# Electric_Mokka_Pot.net
KiCad netlist of a schematic drawn in EasyEDA
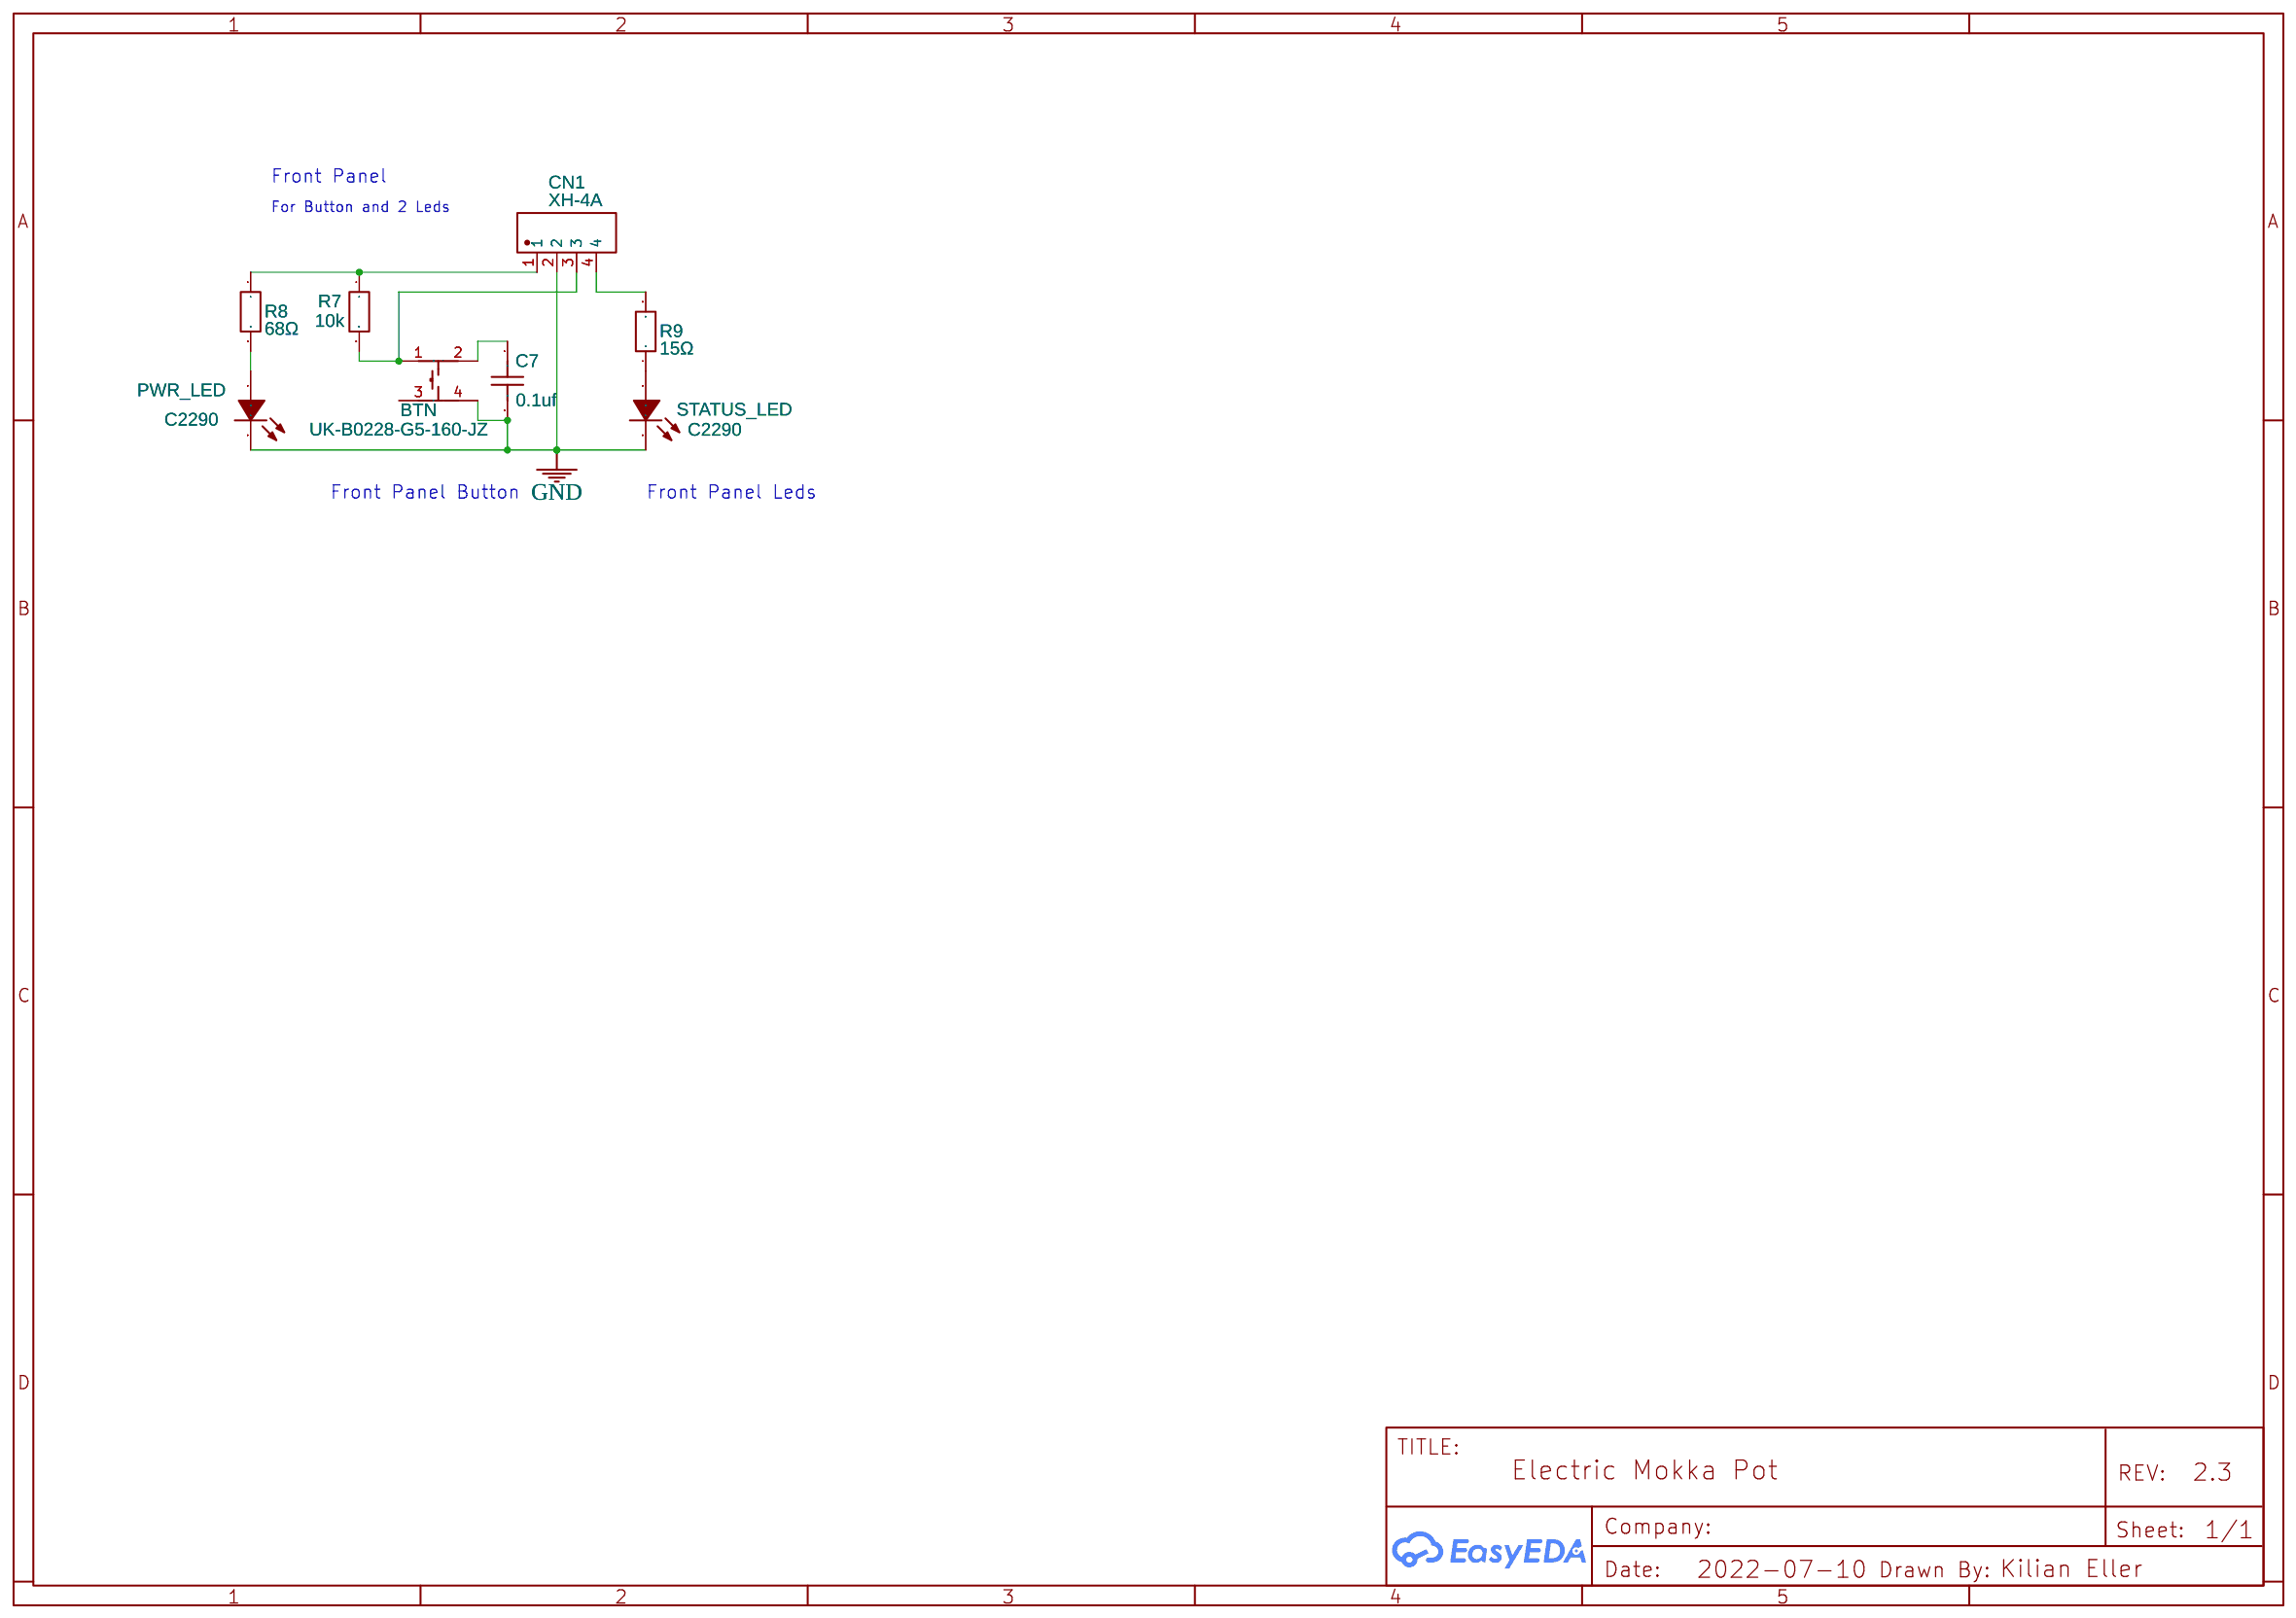
[diagram p0: schematic sheet]

(export (version "E")
  (design (tool "Eeschema 10.0.6"))
  (components
    (comp (ref "BTN")
      (value "UK-B0228-G5-160-JZ")
      (fields (field (name "BOM_Supplier Part") "C620316"))
      (libsource (lib "") (part "UK-B0228-G5-160-JZ"))
    )
    (comp (ref "C7") (value "0.1uf") (libsource (lib "") (part "C_0603_US")))
    (comp (ref "CN1")
      (value "XH-4A")
      (fields (field (name "BOM_Manufacturer Part") "XH-4A 黄色") (field (name "BOM_Supplier Part") "C68117"))
      (libsource (lib "") (part "XH-4A 黄色"))
    )
    (comp (ref "PWR_LED")
      (value "C2290")
      (fields (field (name "BOM_Manufacturer Part") "0603White light"))
      (libsource (lib "") (part "0603White light_C2290"))
    )
    (comp (ref "R7") (value "10k") (libsource (lib "") (part "R_0603_EU")))
    (comp (ref "R8") (value "68Ω") (libsource (lib "") (part "R_0603_EU")))
    (comp (ref "R9") (value "15Ω") (libsource (lib "") (part "R_0603_EU_1")))
    (comp (ref "STATUS_LED")
      (value "C2290")
      (fields (field (name "BOM_Manufacturer Part") "0603White light"))
      (libsource (lib "") (part "0603White light_C2290_1"))
    )
  )
  (nets
    (net (code "1") (name "GND") (class "Default")
      (node (ref "BTN") (pin "4") (pinfunction "4_4") (pintype "unspecified"))
      (node (ref "C7") (pin "2") (pinfunction "2_2") (pintype "unspecified"))
      (node (ref "CN1") (pin "2") (pinfunction "2_2") (pintype "unspecified"))
      (node (ref "PWR_LED") (pin "2") (pinfunction "K_2") (pintype "unspecified"))
      (node (ref "STATUS_LED") (pin "2") (pinfunction "K_2") (pintype "unspecified"))
    )
    (net (code "2") (name "Net-(BTN-Pad1)") (class "Default")
      (node (ref "BTN") (pin "1") (pinfunction "1_1") (pintype "unspecified"))
      (node (ref "CN1") (pin "3") (pinfunction "3_3") (pintype "unspecified"))
      (node (ref "R7") (pin "2") (pinfunction "2_2") (pintype "unspecified"))
    )
    (net (code "3") (name "Net-(BTN-Pad2)") (class "Default")
      (node (ref "BTN") (pin "2") (pinfunction "2_2") (pintype "unspecified"))
      (node (ref "C7") (pin "1") (pinfunction "1_1") (pintype "unspecified"))
    )
    (net (code "4") (name "Net-(CN1-Pad1)") (class "Default")
      (node (ref "CN1") (pin "1") (pinfunction "1_1") (pintype "unspecified"))
      (node (ref "R7") (pin "1") (pinfunction "1_1") (pintype "unspecified"))
      (node (ref "R8") (pin "1") (pinfunction "1_1") (pintype "unspecified"))
    )
    (net (code "5") (name "Net-(CN1-Pad4)") (class "Default")
      (node (ref "CN1") (pin "4") (pinfunction "4_4") (pintype "unspecified"))
      (node (ref "R9") (pin "2") (pinfunction "2_2") (pintype "unspecified"))
    )
    (net (code "6") (name "Net-(PWR_LED-A)") (class "Default")
      (node (ref "PWR_LED") (pin "1") (pinfunction "A_1") (pintype "unspecified"))
      (node (ref "R8") (pin "2") (pinfunction "2_2") (pintype "unspecified"))
    )
    (net (code "7") (name "Net-(STATUS_LED-A)") (class "Default")
      (node (ref "R9") (pin "1") (pinfunction "1_1") (pintype "unspecified"))
      (node (ref "STATUS_LED") (pin "1") (pinfunction "A_1") (pintype "unspecified"))
    )
    (net (code "8") (name "unconnected-(BTN-Pad3)") (class "Default")
      (node (ref "BTN") (pin "3") (pinfunction "3_3") (pintype "unspecified"))
    )
  )
)
